# ACQ.net
KiCad netlist of a schematic drawn in Altium Designer
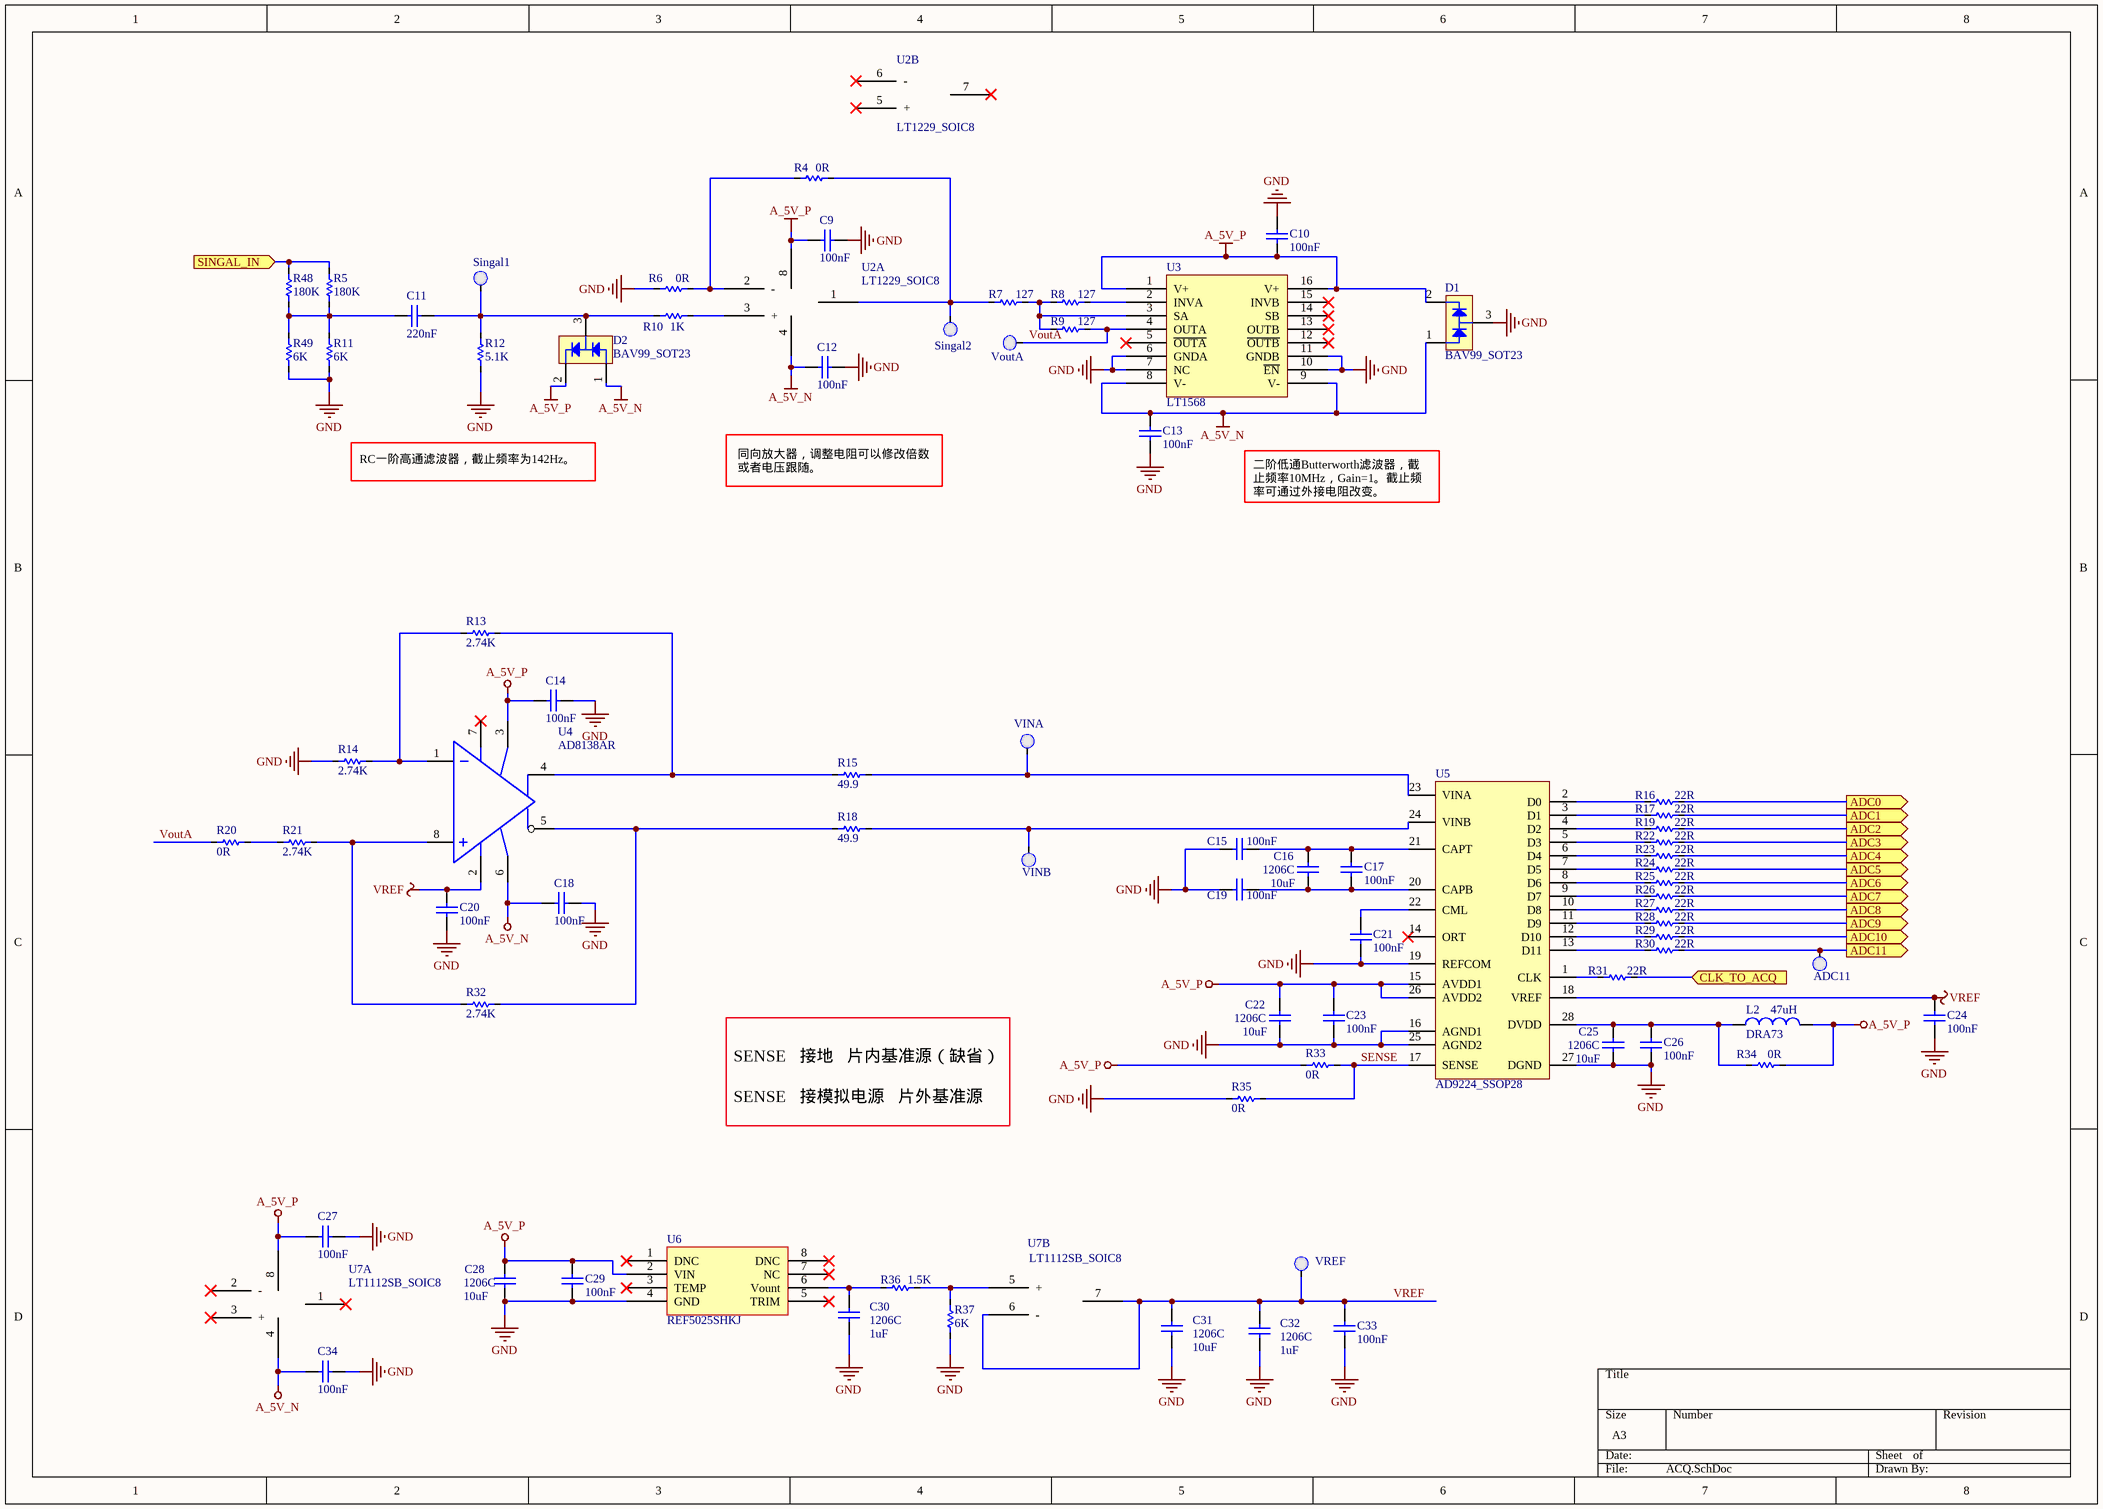
[diagram p0: ACQ.SchDoc]

(export (version "E")
  (design (tool "Eeschema 10.0.6"))
  (components
    (comp (ref "ADC11") (value "TP") (footprint "TPA") (libsource (lib "STM32") (part "TP")))
    (comp (ref "C9")
      (value "100nF")
      (footprint "0805C")
      (description "Capacitor")
      (fields (field (name "PUBLISHER") "Altium Limited"))
      (libsource (lib "STM32") (part "Cap"))
    )
    (comp (ref "C10")
      (value "100nF")
      (footprint "0805C")
      (description "Capacitor")
      (fields (field (name "PUBLISHER") "Altium Limited"))
      (libsource (lib "STM32") (part "Cap"))
    )
    (comp (ref "C11")
      (value "220nF")
      (footprint "0805C")
      (description "Capacitor")
      (fields (field (name "PUBLISHER") "Altium Limited"))
      (libsource (lib "STM32") (part "Cap"))
    )
    (comp (ref "C12")
      (value "100nF")
      (footprint "0805C")
      (description "Capacitor")
      (fields (field (name "PUBLISHER") "Altium Limited"))
      (libsource (lib "STM32") (part "Cap"))
    )
    (comp (ref "C13")
      (value "100nF")
      (footprint "0805C")
      (description "Capacitor")
      (fields (field (name "PUBLISHER") "Altium Limited"))
      (libsource (lib "STM32") (part "Cap"))
    )
    (comp (ref "C14")
      (value "100nF")
      (footprint "0805C")
      (description "Capacitor")
      (fields (field (name "PUBLISHER") "Altium Limited"))
      (libsource (lib "STM32") (part "Cap"))
    )
    (comp (ref "C15")
      (value "100nF")
      (footprint "0805C")
      (description "Capacitor")
      (fields (field (name "PUBLISHER") "Altium Limited"))
      (libsource (lib "STM32") (part "Cap"))
    )
    (comp (ref "C16")
      (value "10uF")
      (footprint "1206C")
      (description "Capacitor")
      (fields (field (name "PACKAGEREFERENCE") "1206C") (field (name "PUBLISHER") "Altium Limited"))
      (libsource (lib "STM32") (part "Cap"))
    )
    (comp (ref "C17")
      (value "100nF")
      (footprint "0805C")
      (description "Capacitor")
      (fields (field (name "PUBLISHER") "Altium Limited"))
      (libsource (lib "STM32") (part "Cap"))
    )
    (comp (ref "C18")
      (value "100nF")
      (footprint "0805C")
      (description "Capacitor")
      (fields (field (name "PUBLISHER") "Altium Limited"))
      (libsource (lib "STM32") (part "Cap"))
    )
    (comp (ref "C19")
      (value "100nF")
      (footprint "0805C")
      (description "Capacitor")
      (fields (field (name "PUBLISHER") "Altium Limited"))
      (libsource (lib "STM32") (part "Cap"))
    )
    (comp (ref "C20")
      (value "100nF")
      (footprint "0805C")
      (description "Capacitor")
      (fields (field (name "PUBLISHER") "Altium Limited"))
      (libsource (lib "STM32") (part "Cap"))
    )
    (comp (ref "C21")
      (value "100nF")
      (footprint "0805C")
      (description "Capacitor")
      (fields (field (name "PUBLISHER") "Altium Limited"))
      (libsource (lib "STM32") (part "Cap"))
    )
    (comp (ref "C22")
      (value "10uF")
      (footprint "1206C")
      (description "Capacitor")
      (fields (field (name "PACKAGEREFERENCE") "1206C") (field (name "PUBLISHER") "Altium Limited"))
      (libsource (lib "STM32") (part "Cap"))
    )
    (comp (ref "C23")
      (value "100nF")
      (footprint "0805C")
      (description "Capacitor")
      (fields (field (name "PUBLISHER") "Altium Limited"))
      (libsource (lib "STM32") (part "Cap"))
    )
    (comp (ref "C24")
      (value "100nF")
      (footprint "0805C")
      (description "Capacitor")
      (fields (field (name "PUBLISHER") "Altium Limited"))
      (libsource (lib "STM32") (part "Cap"))
    )
    (comp (ref "C25")
      (value "10uF")
      (footprint "1206C")
      (description "Capacitor")
      (fields (field (name "PACKAGEREFERENCE") "1206C") (field (name "PUBLISHER") "Altium Limited"))
      (libsource (lib "STM32") (part "Cap"))
    )
    (comp (ref "C26")
      (value "100nF")
      (footprint "0805C")
      (description "Capacitor")
      (fields (field (name "PUBLISHER") "Altium Limited"))
      (libsource (lib "STM32") (part "Cap"))
    )
    (comp (ref "C27")
      (value "100nF")
      (footprint "0805C")
      (description "Capacitor")
      (fields (field (name "PUBLISHER") "Altium Limited"))
      (libsource (lib "STM32") (part "Cap"))
    )
    (comp (ref "C28")
      (value "10uF")
      (footprint "1206C")
      (description "Capacitor")
      (fields (field (name "PACKAGEREFERENCE") "1206C") (field (name "PUBLISHER") "Altium Limited"))
      (libsource (lib "STM32") (part "Cap"))
    )
    (comp (ref "C29")
      (value "100nF")
      (footprint "0805C")
      (description "Capacitor")
      (fields (field (name "PUBLISHER") "Altium Limited"))
      (libsource (lib "STM32") (part "Cap"))
    )
    (comp (ref "C30")
      (value "1uF")
      (footprint "1206C")
      (description "Capacitor")
      (fields (field (name "PACKAGEREFERENCE") "1206C") (field (name "PUBLISHER") "Altium Limited"))
      (libsource (lib "STM32") (part "Cap"))
    )
    (comp (ref "C31")
      (value "10uF")
      (footprint "1206C")
      (description "Capacitor")
      (fields (field (name "PACKAGEREFERENCE") "1206C") (field (name "PUBLISHER") "Altium Limited"))
      (libsource (lib "STM32") (part "Cap"))
    )
    (comp (ref "C32")
      (value "1uF")
      (footprint "1206C")
      (description "Capacitor")
      (fields (field (name "PACKAGEREFERENCE") "1206C") (field (name "PUBLISHER") "Altium Limited"))
      (libsource (lib "STM32") (part "Cap"))
    )
    (comp (ref "C33")
      (value "100nF")
      (footprint "0805C")
      (description "Capacitor")
      (fields (field (name "PUBLISHER") "Altium Limited"))
      (libsource (lib "STM32") (part "Cap"))
    )
    (comp (ref "C34")
      (value "100nF")
      (footprint "0805C")
      (description "Capacitor")
      (fields (field (name "PUBLISHER") "Altium Limited"))
      (libsource (lib "STM32") (part "Cap"))
    )
    (comp (ref "D1") (value "BAV99_SOT23") (footprint "SOT23-3N") (libsource (lib "STM32") (part "BAV99LT1")))
    (comp (ref "D2") (value "BAV99_SOT23") (footprint "SOT23-3N") (libsource (lib "") (part "BAV99LT1_1")))
    (comp (ref "L2")
      (value "DRA73")
      (footprint "INDP7676X35N")
      (description "Inductor")
      (fields (field (name "ALTIUM_VALUE") "47uH"))
      (libsource (lib "STM32") (part "Inductor"))
    )
    (comp (ref "R4")
      (value "0R")
      (footprint "0805R")
      (description "Resistor")
      (fields (field (name "PUBLISHER") "Altium Limited"))
      (libsource (lib "STM32") (part "Res1"))
    )
    (comp (ref "R5")
      (value "180K")
      (footprint "0805R")
      (description "Resistor")
      (fields (field (name "PUBLISHER") "Altium Limited"))
      (libsource (lib "STM32") (part "Res1"))
    )
    (comp (ref "R6")
      (value "0R")
      (footprint "0805R")
      (description "Resistor")
      (fields (field (name "PUBLISHER") "Altium Limited"))
      (libsource (lib "STM32") (part "Res1"))
    )
    (comp (ref "R7")
      (value "127")
      (footprint "0805R")
      (description "Resistor")
      (fields (field (name "PUBLISHER") "Altium Limited"))
      (libsource (lib "STM32") (part "Res1"))
    )
    (comp (ref "R8")
      (value "127")
      (footprint "0805R")
      (description "Resistor")
      (fields (field (name "PUBLISHER") "Altium Limited"))
      (libsource (lib "STM32") (part "Res1"))
    )
    (comp (ref "R9")
      (value "127")
      (footprint "0805R")
      (description "Resistor")
      (fields (field (name "PUBLISHER") "Altium Limited"))
      (libsource (lib "STM32") (part "Res1"))
    )
    (comp (ref "R10")
      (value "1K")
      (footprint "0805R")
      (description "Resistor")
      (fields (field (name "PUBLISHER") "Altium Limited"))
      (libsource (lib "STM32") (part "Res1"))
    )
    (comp (ref "R11")
      (value "6K")
      (footprint "0805R")
      (description "Resistor")
      (fields (field (name "PUBLISHER") "Altium Limited"))
      (libsource (lib "STM32") (part "Res1"))
    )
    (comp (ref "R12")
      (value "5.1K")
      (footprint "0805R")
      (description "Resistor")
      (fields (field (name "PUBLISHER") "Altium Limited"))
      (libsource (lib "STM32") (part "Res1"))
    )
    (comp (ref "R13")
      (value "2.74K")
      (footprint "0805R")
      (description "Resistor")
      (fields (field (name "PUBLISHER") "Altium Limited"))
      (libsource (lib "STM32") (part "Res1"))
    )
    (comp (ref "R14")
      (value "2.74K")
      (footprint "0805R")
      (description "Resistor")
      (fields (field (name "PUBLISHER") "Altium Limited"))
      (libsource (lib "STM32") (part "Res1"))
    )
    (comp (ref "R15")
      (value "49.9")
      (footprint "0805R")
      (description "Resistor")
      (fields (field (name "PUBLISHER") "Altium Limited"))
      (libsource (lib "STM32") (part "Res1"))
    )
    (comp (ref "R16")
      (value "22R")
      (footprint "0805R")
      (description "Resistor")
      (fields (field (name "PUBLISHER") "Altium Limited"))
      (libsource (lib "STM32") (part "Res1"))
    )
    (comp (ref "R17")
      (value "22R")
      (footprint "0805R")
      (description "Resistor")
      (fields (field (name "PUBLISHER") "Altium Limited"))
      (libsource (lib "STM32") (part "Res1"))
    )
    (comp (ref "R18")
      (value "49.9")
      (footprint "0805R")
      (description "Resistor")
      (fields (field (name "PUBLISHER") "Altium Limited"))
      (libsource (lib "STM32") (part "Res1"))
    )
    (comp (ref "R19")
      (value "22R")
      (footprint "0805R")
      (description "Resistor")
      (fields (field (name "PUBLISHER") "Altium Limited"))
      (libsource (lib "STM32") (part "Res1"))
    )
    (comp (ref "R20")
      (value "0R")
      (footprint "0805R")
      (description "Resistor")
      (fields (field (name "PUBLISHER") "Altium Limited"))
      (libsource (lib "STM32") (part "Res1"))
    )
    (comp (ref "R21")
      (value "2.74K")
      (footprint "0805R")
      (description "Resistor")
      (fields (field (name "PUBLISHER") "Altium Limited"))
      (libsource (lib "STM32") (part "Res1"))
    )
    (comp (ref "R22")
      (value "22R")
      (footprint "0805R")
      (description "Resistor")
      (fields (field (name "PUBLISHER") "Altium Limited"))
      (libsource (lib "STM32") (part "Res1"))
    )
    (comp (ref "R23")
      (value "22R")
      (footprint "0805R")
      (description "Resistor")
      (fields (field (name "PUBLISHER") "Altium Limited"))
      (libsource (lib "STM32") (part "Res1"))
    )
    (comp (ref "R24")
      (value "22R")
      (footprint "0805R")
      (description "Resistor")
      (fields (field (name "PUBLISHER") "Altium Limited"))
      (libsource (lib "STM32") (part "Res1"))
    )
    (comp (ref "R25")
      (value "22R")
      (footprint "0805R")
      (description "Resistor")
      (fields (field (name "PUBLISHER") "Altium Limited"))
      (libsource (lib "STM32") (part "Res1"))
    )
    (comp (ref "R26")
      (value "22R")
      (footprint "0805R")
      (description "Resistor")
      (fields (field (name "PUBLISHER") "Altium Limited"))
      (libsource (lib "STM32") (part "Res1"))
    )
    (comp (ref "R27")
      (value "22R")
      (footprint "0805R")
      (description "Resistor")
      (fields (field (name "PUBLISHER") "Altium Limited"))
      (libsource (lib "STM32") (part "Res1"))
    )
    (comp (ref "R28")
      (value "22R")
      (footprint "0805R")
      (description "Resistor")
      (fields (field (name "PUBLISHER") "Altium Limited"))
      (libsource (lib "STM32") (part "Res1"))
    )
    (comp (ref "R29")
      (value "22R")
      (footprint "0805R")
      (description "Resistor")
      (fields (field (name "PUBLISHER") "Altium Limited"))
      (libsource (lib "STM32") (part "Res1"))
    )
    (comp (ref "R30")
      (value "22R")
      (footprint "0805R")
      (description "Resistor")
      (fields (field (name "PUBLISHER") "Altium Limited"))
      (libsource (lib "STM32") (part "Res1"))
    )
    (comp (ref "R31")
      (value "22R")
      (footprint "0805R")
      (description "Resistor")
      (fields (field (name "PUBLISHER") "Altium Limited"))
      (libsource (lib "STM32") (part "Res1"))
    )
    (comp (ref "R32")
      (value "2.74K")
      (footprint "0805R")
      (description "Resistor")
      (fields (field (name "PUBLISHER") "Altium Limited"))
      (libsource (lib "STM32") (part "Res1"))
    )
    (comp (ref "R33")
      (value "0R")
      (footprint "0805R")
      (description "Resistor")
      (fields (field (name "PUBLISHER") "Altium Limited"))
      (libsource (lib "STM32") (part "Res1"))
    )
    (comp (ref "R34")
      (value "0R")
      (footprint "0805R")
      (description "Resistor")
      (fields (field (name "PUBLISHER") "Altium Limited"))
      (libsource (lib "STM32") (part "Res1"))
    )
    (comp (ref "R35")
      (value "0R")
      (footprint "0805R")
      (description "Resistor")
      (fields (field (name "PUBLISHER") "Altium Limited"))
      (libsource (lib "STM32") (part "Res1"))
    )
    (comp (ref "R36")
      (value "1.5K")
      (footprint "0805R")
      (description "Resistor")
      (fields (field (name "PUBLISHER") "Altium Limited"))
      (libsource (lib "STM32") (part "Res1"))
    )
    (comp (ref "R37")
      (value "6K")
      (footprint "0805R")
      (description "Resistor")
      (fields (field (name "PUBLISHER") "Altium Limited"))
      (libsource (lib "STM32") (part "Res1"))
    )
    (comp (ref "R48")
      (value "180K")
      (footprint "0805R")
      (description "Resistor")
      (fields (field (name "PUBLISHER") "Altium Limited"))
      (libsource (lib "STM32") (part "Res1"))
    )
    (comp (ref "R49")
      (value "6K")
      (footprint "0805R")
      (description "Resistor")
      (fields (field (name "PUBLISHER") "Altium Limited"))
      (libsource (lib "STM32") (part "Res1"))
    )
    (comp (ref "Singal1") (value "TP") (footprint "TPA") (libsource (lib "") (part "TP_1")))
    (comp (ref "Singal2") (value "TP") (footprint "TPA") (libsource (lib "STM32") (part "TP")))
    (comp (ref "U2") (value "LT1229_SOIC8") (footprint "SO-8") (libsource (lib "STM32") (part "AD827")))
    (comp (ref "U3") (value "LT1568") (footprint "SSOP16") (libsource (lib "STM32") (part "LT1568")))
    (comp (ref "U4") (value "AD8138AR") (footprint "SO-8") (libsource (lib "STM32") (part "AD8138AR")))
    (comp (ref "U5") (value "AD9224_SSOP28") (footprint "TSSOP28") (libsource (lib "STM32") (part "AD9224")))
    (comp (ref "U6")
      (value "REF5025SHKJ")
      (footprint "SO8-HKJ")
      (libsource (lib "STM32") (part "REF5025SHKJ"))
    )
    (comp (ref "U7") (value "LT1112SB_SOIC8") (footprint "SO-8") (libsource (lib "STM32") (part "AD827")))
    (comp (ref "VINA") (value "TP") (footprint "TPA") (libsource (lib "") (part "TP_1")))
    (comp (ref "VINB") (value "TP") (footprint "TPA") (libsource (lib "STM32") (part "TP")))
    (comp (ref "VoutA") (value "TP") (footprint "TPA") (libsource (lib "") (part "TP_2")))
    (comp (ref "VREF") (value "TP") (footprint "TPA") (libsource (lib "") (part "TP_1")))
  )
  (nets
    (net (code "1") (name "/ADC0") (class "Default")
      (node (ref "R16") (pin "1") (pinfunction "1_1") (pintype "passive"))
    )
    (net (code "2") (name "/ADC1") (class "Default")
      (node (ref "R17") (pin "1") (pinfunction "1_1") (pintype "passive"))
    )
    (net (code "3") (name "/ADC2") (class "Default")
      (node (ref "R19") (pin "1") (pinfunction "1_1") (pintype "passive"))
    )
    (net (code "4") (name "/ADC3") (class "Default")
      (node (ref "R22") (pin "1") (pinfunction "1_1") (pintype "passive"))
    )
    (net (code "5") (name "/ADC4") (class "Default")
      (node (ref "R23") (pin "1") (pinfunction "1_1") (pintype "passive"))
    )
    (net (code "6") (name "/ADC5") (class "Default")
      (node (ref "R24") (pin "1") (pinfunction "1_1") (pintype "passive"))
    )
    (net (code "7") (name "/ADC6") (class "Default")
      (node (ref "R25") (pin "1") (pinfunction "1_1") (pintype "passive"))
    )
    (net (code "8") (name "/ADC7") (class "Default")
      (node (ref "R26") (pin "1") (pinfunction "1_1") (pintype "passive"))
    )
    (net (code "9") (name "/ADC8") (class "Default")
      (node (ref "R27") (pin "1") (pinfunction "1_1") (pintype "passive"))
    )
    (net (code "10") (name "/ADC9") (class "Default")
      (node (ref "R28") (pin "1") (pinfunction "1_1") (pintype "passive"))
    )
    (net (code "11") (name "/ADC10") (class "Default")
      (node (ref "R29") (pin "1") (pinfunction "1_1") (pintype "passive"))
    )
    (net (code "12") (name "/ADC11") (class "Default")
      (node (ref "ADC11") (pin "1") (pinfunction "TP_1") (pintype "passive"))
      (node (ref "R30") (pin "1") (pinfunction "1_1") (pintype "passive"))
    )
    (net (code "13") (name "/CLK_TO_ACQ") (class "Default")
      (node (ref "R31") (pin "1") (pinfunction "1_1") (pintype "passive"))
    )
    (net (code "14") (name "/SENSE") (class "Default")
      (node (ref "R33") (pin "1") (pinfunction "1_1") (pintype "passive"))
      (node (ref "R35") (pin "1") (pinfunction "1_1") (pintype "passive"))
      (node (ref "U5") (pin "17") (pinfunction "SENSE_17") (pintype "passive"))
    )
    (net (code "15") (name "/SINGAL_IN") (class "Default")
      (node (ref "R48") (pin "2") (pinfunction "2_2") (pintype "passive"))
      (node (ref "R5") (pin "2") (pinfunction "2_2") (pintype "passive"))
    )
    (net (code "16") (name "/VoutA") (class "Default")
      (node (ref "R20") (pin "2") (pinfunction "2_2") (pintype "passive"))
      (node (ref "R9") (pin "2") (pinfunction "2_2") (pintype "passive"))
      (node (ref "U3") (pin "4") (pinfunction "OUTA_4") (pintype "passive"))
      (node (ref "VoutA") (pin "1") (pinfunction "TP_1") (pintype "passive"))
    )
    (net (code "17") (name "A_5V_N") (class "Default")
      (node (ref "C12") (pin "2") (pinfunction "2_2") (pintype "passive"))
      (node (ref "C13") (pin "2") (pinfunction "2_2") (pintype "passive"))
      (node (ref "C18") (pin "1") (pinfunction "1_1") (pintype "passive"))
      (node (ref "C34") (pin "2") (pinfunction "2_2") (pintype "passive"))
      (node (ref "D1") (pin "1") (pinfunction "1_1") (pintype "passive"))
      (node (ref "D2") (pin "1") (pinfunction "1_1") (pintype "passive"))
      (node (ref "U2") (pin "4") (pintype "passive"))
      (node (ref "U3") (pin "8") (pinfunction "V-_8") (pintype "passive"))
      (node (ref "U3") (pin "9") (pinfunction "V-_9") (pintype "passive"))
      (node (ref "U4") (pin "6") (pinfunction "V-_6") (pintype "power_in"))
      (node (ref "U7") (pin "4") (pintype "passive"))
    )
    (net (code "18") (name "A_5V_P") (class "Default")
      (node (ref "C10") (pin "1") (pinfunction "1_1") (pintype "passive"))
      (node (ref "C14") (pin "1") (pinfunction "1_1") (pintype "passive"))
      (node (ref "C22") (pin "2") (pinfunction "2_2") (pintype "passive"))
      (node (ref "C23") (pin "1") (pinfunction "1_1") (pintype "passive"))
      (node (ref "C27") (pin "1") (pinfunction "1_1") (pintype "passive"))
      (node (ref "C28") (pin "2") (pinfunction "2_2") (pintype "passive"))
      (node (ref "C29") (pin "1") (pinfunction "1_1") (pintype "passive"))
      (node (ref "C9") (pin "2") (pinfunction "2_2") (pintype "passive"))
      (node (ref "D1") (pin "2") (pinfunction "2_2") (pintype "passive"))
      (node (ref "D2") (pin "2") (pinfunction "2_2") (pintype "passive"))
      (node (ref "L2") (pin "2") (pinfunction "2_2") (pintype "passive"))
      (node (ref "R33") (pin "2") (pinfunction "2_2") (pintype "passive"))
      (node (ref "R34") (pin "1") (pinfunction "1_1") (pintype "passive"))
      (node (ref "U2") (pin "8") (pintype "passive"))
      (node (ref "U3") (pin "1") (pinfunction "V+_1") (pintype "passive"))
      (node (ref "U3") (pin "16") (pinfunction "V+_16") (pintype "passive"))
      (node (ref "U4") (pin "3") (pinfunction "V+_3") (pintype "power_in"))
      (node (ref "U5") (pin "15") (pinfunction "AVDD1_15") (pintype "passive"))
      (node (ref "U5") (pin "26") (pinfunction "AVDD2_26") (pintype "passive"))
      (node (ref "U6") (pin "2") (pinfunction "VIN_2") (pintype "passive"))
      (node (ref "U7") (pin "8") (pintype "passive"))
    )
    (net (code "19") (name "GND") (class "Default")
      (node (ref "C10") (pin "2") (pinfunction "2_2") (pintype "passive"))
      (node (ref "C12") (pin "1") (pinfunction "1_1") (pintype "passive"))
      (node (ref "C13") (pin "1") (pinfunction "1_1") (pintype "passive"))
      (node (ref "C14") (pin "2") (pinfunction "2_2") (pintype "passive"))
      (node (ref "C15") (pin "1") (pinfunction "1_1") (pintype "passive"))
      (node (ref "C18") (pin "2") (pinfunction "2_2") (pintype "passive"))
      (node (ref "C19") (pin "1") (pinfunction "1_1") (pintype "passive"))
      (node (ref "C20") (pin "2") (pinfunction "2_2") (pintype "passive"))
      (node (ref "C21") (pin "2") (pinfunction "2_2") (pintype "passive"))
      (node (ref "C22") (pin "1") (pinfunction "1_1") (pintype "passive"))
      (node (ref "C23") (pin "2") (pinfunction "2_2") (pintype "passive"))
      (node (ref "C24") (pin "2") (pinfunction "2_2") (pintype "passive"))
      (node (ref "C25") (pin "1") (pinfunction "1_1") (pintype "passive"))
      (node (ref "C26") (pin "2") (pinfunction "2_2") (pintype "passive"))
      (node (ref "C27") (pin "2") (pinfunction "2_2") (pintype "passive"))
      (node (ref "C28") (pin "1") (pinfunction "1_1") (pintype "passive"))
      (node (ref "C29") (pin "2") (pinfunction "2_2") (pintype "passive"))
      (node (ref "C30") (pin "1") (pinfunction "1_1") (pintype "passive"))
      (node (ref "C31") (pin "1") (pinfunction "1_1") (pintype "passive"))
      (node (ref "C32") (pin "1") (pinfunction "1_1") (pintype "passive"))
      (node (ref "C33") (pin "2") (pinfunction "2_2") (pintype "passive"))
      (node (ref "C34") (pin "1") (pinfunction "1_1") (pintype "passive"))
      (node (ref "C9") (pin "1") (pinfunction "1_1") (pintype "passive"))
      (node (ref "D1") (pin "3") (pinfunction "3_3") (pintype "passive"))
      (node (ref "R11") (pin "1") (pinfunction "1_1") (pintype "passive"))
      (node (ref "R12") (pin "1") (pinfunction "1_1") (pintype "passive"))
      (node (ref "R14") (pin "2") (pinfunction "2_2") (pintype "passive"))
      (node (ref "R35") (pin "2") (pinfunction "2_2") (pintype "passive"))
      (node (ref "R37") (pin "1") (pinfunction "1_1") (pintype "passive"))
      (node (ref "R49") (pin "1") (pinfunction "1_1") (pintype "passive"))
      (node (ref "R6") (pin "2") (pinfunction "2_2") (pintype "passive"))
      (node (ref "U3") (pin "10") (pinfunction "~{EN}_10") (pintype "passive"))
      (node (ref "U3") (pin "11") (pinfunction "GNDB_11") (pintype "passive"))
      (node (ref "U3") (pin "6") (pinfunction "GNDA_6") (pintype "passive"))
      (node (ref "U3") (pin "7") (pinfunction "NC_7") (pintype "passive"))
      (node (ref "U5") (pin "16") (pinfunction "AGND1_16") (pintype "passive"))
      (node (ref "U5") (pin "19") (pinfunction "REFCOM_19") (pintype "passive"))
      (node (ref "U5") (pin "25") (pinfunction "AGND2_25") (pintype "passive"))
      (node (ref "U5") (pin "27") (pinfunction "DGND_27") (pintype "passive"))
      (node (ref "U6") (pin "4") (pinfunction "GND_4") (pintype "passive"))
    )
    (net (code "20") (name "Net-(C11-Pad2)") (class "Default")
      (node (ref "C11") (pin "2") (pinfunction "2_2") (pintype "passive"))
      (node (ref "R11") (pin "2") (pinfunction "2_2") (pintype "passive"))
      (node (ref "R48") (pin "1") (pinfunction "1_1") (pintype "passive"))
      (node (ref "R49") (pin "2") (pinfunction "2_2") (pintype "passive"))
      (node (ref "R5") (pin "1") (pinfunction "1_1") (pintype "passive"))
    )
    (net (code "21") (name "Net-(R20-Pad1)") (class "Default")
      (node (ref "R20") (pin "1") (pinfunction "1_1") (pintype "passive"))
      (node (ref "R21") (pin "2") (pinfunction "2_2") (pintype "passive"))
    )
    (net (code "22") (name "Net-(Singal1-TP)") (class "Default")
      (node (ref "C11") (pin "1") (pinfunction "1_1") (pintype "passive"))
      (node (ref "D2") (pin "3") (pinfunction "3_3") (pintype "passive"))
      (node (ref "R10") (pin "2") (pinfunction "2_2") (pintype "passive"))
      (node (ref "R12") (pin "2") (pinfunction "2_2") (pintype "passive"))
      (node (ref "Singal1") (pin "1") (pinfunction "TP_1") (pintype "passive"))
    )
    (net (code "23") (name "Net-(Singal2-TP)") (class "Default")
      (node (ref "R4") (pin "1") (pinfunction "1_1") (pintype "passive"))
      (node (ref "R7") (pin "1") (pinfunction "1_1") (pintype "passive"))
      (node (ref "Singal2") (pin "1") (pinfunction "TP_1") (pintype "passive"))
      (node (ref "U2") (pin "1") (pinfunction "OUTA_1") (pintype "passive"))
    )
    (net (code "24") (name "Net-(U2A-+)") (class "Default")
      (node (ref "R10") (pin "1") (pinfunction "1_1") (pintype "passive"))
      (node (ref "U2") (pin "3") (pinfunction "+_3") (pintype "passive"))
    )
    (net (code "25") (name "Net-(U2A--)") (class "Default")
      (node (ref "R4") (pin "2") (pinfunction "2_2") (pintype "passive"))
      (node (ref "R6") (pin "1") (pinfunction "1_1") (pintype "passive"))
      (node (ref "U2") (pin "2") (pinfunction "-_2") (pintype "passive"))
    )
    (net (code "26") (name "Net-(U3-INVA)") (class "Default")
      (node (ref "R8") (pin "2") (pinfunction "2_2") (pintype "passive"))
      (node (ref "U3") (pin "2") (pinfunction "INVA_2") (pintype "passive"))
    )
    (net (code "27") (name "Net-(U3-SA)") (class "Default")
      (node (ref "R7") (pin "2") (pinfunction "2_2") (pintype "passive"))
      (node (ref "R8") (pin "1") (pinfunction "1_1") (pintype "passive"))
      (node (ref "R9") (pin "1") (pinfunction "1_1") (pintype "passive"))
      (node (ref "U3") (pin "3") (pinfunction "SA_3") (pintype "passive"))
    )
    (net (code "28") (name "Net-(U4-Din+)") (class "Default")
      (node (ref "R21") (pin "1") (pinfunction "1_1") (pintype "passive"))
      (node (ref "R32") (pin "2") (pinfunction "2_2") (pintype "passive"))
      (node (ref "U4") (pin "8") (pinfunction "Din+_8") (pintype "passive"))
    )
    (net (code "29") (name "Net-(U4-Din-)") (class "Default")
      (node (ref "R13") (pin "2") (pinfunction "2_2") (pintype "passive"))
      (node (ref "R14") (pin "1") (pinfunction "1_1") (pintype "passive"))
      (node (ref "U4") (pin "1") (pinfunction "Din-_1") (pintype "passive"))
    )
    (net (code "30") (name "Net-(U4-OUT+)") (class "Default")
      (node (ref "R13") (pin "1") (pinfunction "1_1") (pintype "passive"))
      (node (ref "R15") (pin "2") (pinfunction "2_2") (pintype "passive"))
      (node (ref "U4") (pin "4") (pinfunction "OUT+_4") (pintype "passive"))
    )
    (net (code "31") (name "Net-(U4-OUT-)") (class "Default")
      (node (ref "R18") (pin "2") (pinfunction "2_2") (pintype "passive"))
      (node (ref "R32") (pin "1") (pinfunction "1_1") (pintype "passive"))
      (node (ref "U4") (pin "5") (pinfunction "OUT-_5") (pintype "passive"))
    )
    (net (code "32") (name "Net-(U5-CAPB)") (class "Default")
      (node (ref "C16") (pin "1") (pinfunction "1_1") (pintype "passive"))
      (node (ref "C17") (pin "2") (pinfunction "2_2") (pintype "passive"))
      (node (ref "C19") (pin "2") (pinfunction "2_2") (pintype "passive"))
      (node (ref "U5") (pin "20") (pinfunction "CAPB_20") (pintype "passive"))
    )
    (net (code "33") (name "Net-(U5-CAPT)") (class "Default")
      (node (ref "C15") (pin "2") (pinfunction "2_2") (pintype "passive"))
      (node (ref "C16") (pin "2") (pinfunction "2_2") (pintype "passive"))
      (node (ref "C17") (pin "1") (pinfunction "1_1") (pintype "passive"))
      (node (ref "U5") (pin "21") (pinfunction "CAPT_21") (pintype "passive"))
    )
    (net (code "34") (name "Net-(U5-CLK)") (class "Default")
      (node (ref "R31") (pin "2") (pinfunction "2_2") (pintype "passive"))
      (node (ref "U5") (pin "1") (pinfunction "CLK_1") (pintype "passive"))
    )
    (net (code "35") (name "Net-(U5-CML)") (class "Default")
      (node (ref "C21") (pin "1") (pinfunction "1_1") (pintype "passive"))
      (node (ref "U5") (pin "22") (pinfunction "CML_22") (pintype "passive"))
    )
    (net (code "36") (name "Net-(U5-D0)") (class "Default")
      (node (ref "R16") (pin "2") (pinfunction "2_2") (pintype "passive"))
      (node (ref "U5") (pin "2") (pinfunction "D0_2") (pintype "passive"))
    )
    (net (code "37") (name "Net-(U5-D1)") (class "Default")
      (node (ref "R17") (pin "2") (pinfunction "2_2") (pintype "passive"))
      (node (ref "U5") (pin "3") (pinfunction "D1_3") (pintype "passive"))
    )
    (net (code "38") (name "Net-(U5-D2)") (class "Default")
      (node (ref "R19") (pin "2") (pinfunction "2_2") (pintype "passive"))
      (node (ref "U5") (pin "4") (pinfunction "D2_4") (pintype "passive"))
    )
    (net (code "39") (name "Net-(U5-D3)") (class "Default")
      (node (ref "R22") (pin "2") (pinfunction "2_2") (pintype "passive"))
      (node (ref "U5") (pin "5") (pinfunction "D3_5") (pintype "passive"))
    )
    (net (code "40") (name "Net-(U5-D4)") (class "Default")
      (node (ref "R23") (pin "2") (pinfunction "2_2") (pintype "passive"))
      (node (ref "U5") (pin "6") (pinfunction "D4_6") (pintype "passive"))
    )
    (net (code "41") (name "Net-(U5-D5)") (class "Default")
      (node (ref "R24") (pin "2") (pinfunction "2_2") (pintype "passive"))
      (node (ref "U5") (pin "7") (pinfunction "D5_7") (pintype "passive"))
    )
    (net (code "42") (name "Net-(U5-D6)") (class "Default")
      (node (ref "R25") (pin "2") (pinfunction "2_2") (pintype "passive"))
      (node (ref "U5") (pin "8") (pinfunction "D6_8") (pintype "passive"))
    )
    (net (code "43") (name "Net-(U5-D7)") (class "Default")
      (node (ref "R26") (pin "2") (pinfunction "2_2") (pintype "passive"))
      (node (ref "U5") (pin "9") (pinfunction "D7_9") (pintype "passive"))
    )
    (net (code "44") (name "Net-(U5-D8)") (class "Default")
      (node (ref "R27") (pin "2") (pinfunction "2_2") (pintype "passive"))
      (node (ref "U5") (pin "10") (pinfunction "D8_10") (pintype "passive"))
    )
    (net (code "45") (name "Net-(U5-D9)") (class "Default")
      (node (ref "R28") (pin "2") (pinfunction "2_2") (pintype "passive"))
      (node (ref "U5") (pin "11") (pinfunction "D9_11") (pintype "passive"))
    )
    (net (code "46") (name "Net-(U5-D10)") (class "Default")
      (node (ref "R29") (pin "2") (pinfunction "2_2") (pintype "passive"))
      (node (ref "U5") (pin "12") (pinfunction "D10_12") (pintype "passive"))
    )
    (net (code "47") (name "Net-(U5-D11)") (class "Default")
      (node (ref "R30") (pin "2") (pinfunction "2_2") (pintype "passive"))
      (node (ref "U5") (pin "13") (pinfunction "D11_13") (pintype "passive"))
    )
    (net (code "48") (name "Net-(U5-DVDD)") (class "Default")
      (node (ref "C25") (pin "2") (pinfunction "2_2") (pintype "passive"))
      (node (ref "C26") (pin "1") (pinfunction "1_1") (pintype "passive"))
      (node (ref "L2") (pin "1") (pinfunction "1_1") (pintype "passive"))
      (node (ref "R34") (pin "2") (pinfunction "2_2") (pintype "passive"))
      (node (ref "U5") (pin "28") (pinfunction "DVDD_28") (pintype "passive"))
    )
    (net (code "49") (name "Net-(U5-VINA)") (class "Default")
      (node (ref "R15") (pin "1") (pinfunction "1_1") (pintype "passive"))
      (node (ref "U5") (pin "23") (pinfunction "VINA_23") (pintype "passive"))
      (node (ref "VINA") (pin "1") (pinfunction "TP_1") (pintype "passive"))
    )
    (net (code "50") (name "Net-(U5-VINB)") (class "Default")
      (node (ref "R18") (pin "1") (pinfunction "1_1") (pintype "passive"))
      (node (ref "U5") (pin "24") (pinfunction "VINB_24") (pintype "passive"))
      (node (ref "VINB") (pin "1") (pinfunction "TP_1") (pintype "passive"))
    )
    (net (code "51") (name "Net-(U6-Vount)") (class "Default")
      (node (ref "C30") (pin "2") (pinfunction "2_2") (pintype "passive"))
      (node (ref "R36") (pin "1") (pinfunction "1_1") (pintype "passive"))
      (node (ref "U6") (pin "6") (pinfunction "Vount_6") (pintype "passive"))
    )
    (net (code "52") (name "Net-(U7B-+)") (class "Default")
      (node (ref "R36") (pin "2") (pinfunction "2_2") (pintype "passive"))
      (node (ref "R37") (pin "2") (pinfunction "2_2") (pintype "passive"))
      (node (ref "U7") (pin "5") (pinfunction "+_5") (pintype "passive"))
    )
    (net (code "53") (name "VREF") (class "Default")
      (node (ref "C20") (pin "1") (pinfunction "1_1") (pintype "passive"))
      (node (ref "C24") (pin "1") (pinfunction "1_1") (pintype "passive"))
      (node (ref "C31") (pin "2") (pinfunction "2_2") (pintype "passive"))
      (node (ref "C32") (pin "2") (pinfunction "2_2") (pintype "passive"))
      (node (ref "C33") (pin "1") (pinfunction "1_1") (pintype "passive"))
      (node (ref "U4") (pin "2") (pinfunction "Vcom_2") (pintype "passive"))
      (node (ref "U5") (pin "18") (pinfunction "VREF_18") (pintype "passive"))
      (node (ref "U7") (pin "6") (pinfunction "-_6") (pintype "passive"))
      (node (ref "U7") (pin "7") (pinfunction "OUTB_7") (pintype "passive"))
      (node (ref "VREF") (pin "1") (pinfunction "TP_1") (pintype "passive"))
    )
    (net (code "54") (name "unconnected-(U2B-+-Pad5)") (class "Default")
      (node (ref "U2") (pin "5") (pinfunction "+_5") (pintype "passive+no_connect"))
    )
    (net (code "55") (name "unconnected-(U2B---Pad6)") (class "Default")
      (node (ref "U2") (pin "6") (pinfunction "-_6") (pintype "passive+no_connect"))
    )
    (net (code "56") (name "unconnected-(U2B-OUTB-Pad7)") (class "Default")
      (node (ref "U2") (pin "7") (pinfunction "OUTB_7") (pintype "passive+no_connect"))
    )
    (net (code "57") (name "unconnected-(U3-INVB-Pad15)") (class "Default")
      (node (ref "U3") (pin "15") (pinfunction "INVB_15") (pintype "passive+no_connect"))
    )
    (net (code "58") (name "unconnected-(U3-OUTB-Pad13)") (class "Default")
      (node (ref "U3") (pin "13") (pinfunction "OUTB_13") (pintype "passive+no_connect"))
    )
    (net (code "59") (name "unconnected-(U3-SB-Pad14)") (class "Default")
      (node (ref "U3") (pin "14") (pinfunction "SB_14") (pintype "passive+no_connect"))
    )
    (net (code "60") (name "unconnected-(U3-~{OUTA}-Pad5)") (class "Default")
      (node (ref "U3") (pin "5") (pinfunction "~{OUTA}_5") (pintype "passive+no_connect"))
    )
    (net (code "61") (name "unconnected-(U3-~{OUTB}-Pad12)") (class "Default")
      (node (ref "U3") (pin "12") (pinfunction "~{OUTB}_12") (pintype "passive+no_connect"))
    )
    (net (code "62") (name "unconnected-(U4-NC-Pad7)") (class "Default")
      (node (ref "U4") (pin "7") (pinfunction "NC_7") (pintype "passive+no_connect"))
    )
    (net (code "63") (name "unconnected-(U5-ORT-Pad14)") (class "Default")
      (node (ref "U5") (pin "14") (pinfunction "ORT_14") (pintype "passive+no_connect"))
    )
    (net (code "64") (name "unconnected-(U6-DNC-Pad1)") (class "Default")
      (node (ref "U6") (pin "1") (pinfunction "DNC_1") (pintype "passive+no_connect"))
    )
    (net (code "65") (name "unconnected-(U6-DNC-Pad8)") (class "Default")
      (node (ref "U6") (pin "8") (pinfunction "DNC_8") (pintype "passive+no_connect"))
    )
    (net (code "66") (name "unconnected-(U6-NC-Pad7)") (class "Default")
      (node (ref "U6") (pin "7") (pinfunction "NC_7") (pintype "passive+no_connect"))
    )
    (net (code "67") (name "unconnected-(U6-TEMP-Pad3)") (class "Default")
      (node (ref "U6") (pin "3") (pinfunction "TEMP_3") (pintype "passive+no_connect"))
    )
    (net (code "68") (name "unconnected-(U6-TRIM-Pad5)") (class "Default")
      (node (ref "U6") (pin "5") (pinfunction "TRIM_5") (pintype "passive+no_connect"))
    )
    (net (code "69") (name "unconnected-(U7A-+-Pad3)") (class "Default")
      (node (ref "U7") (pin "3") (pinfunction "+_3") (pintype "passive+no_connect"))
    )
    (net (code "70") (name "unconnected-(U7A---Pad2)") (class "Default")
      (node (ref "U7") (pin "2") (pinfunction "-_2") (pintype "passive+no_connect"))
    )
    (net (code "71") (name "unconnected-(U7A-OUTA-Pad1)") (class "Default")
      (node (ref "U7") (pin "1") (pinfunction "OUTA_1") (pintype "passive+no_connect"))
    )
  )
)
